# PPR_1_MP.net
KiCad netlist of a schematic drawn in EAGLE
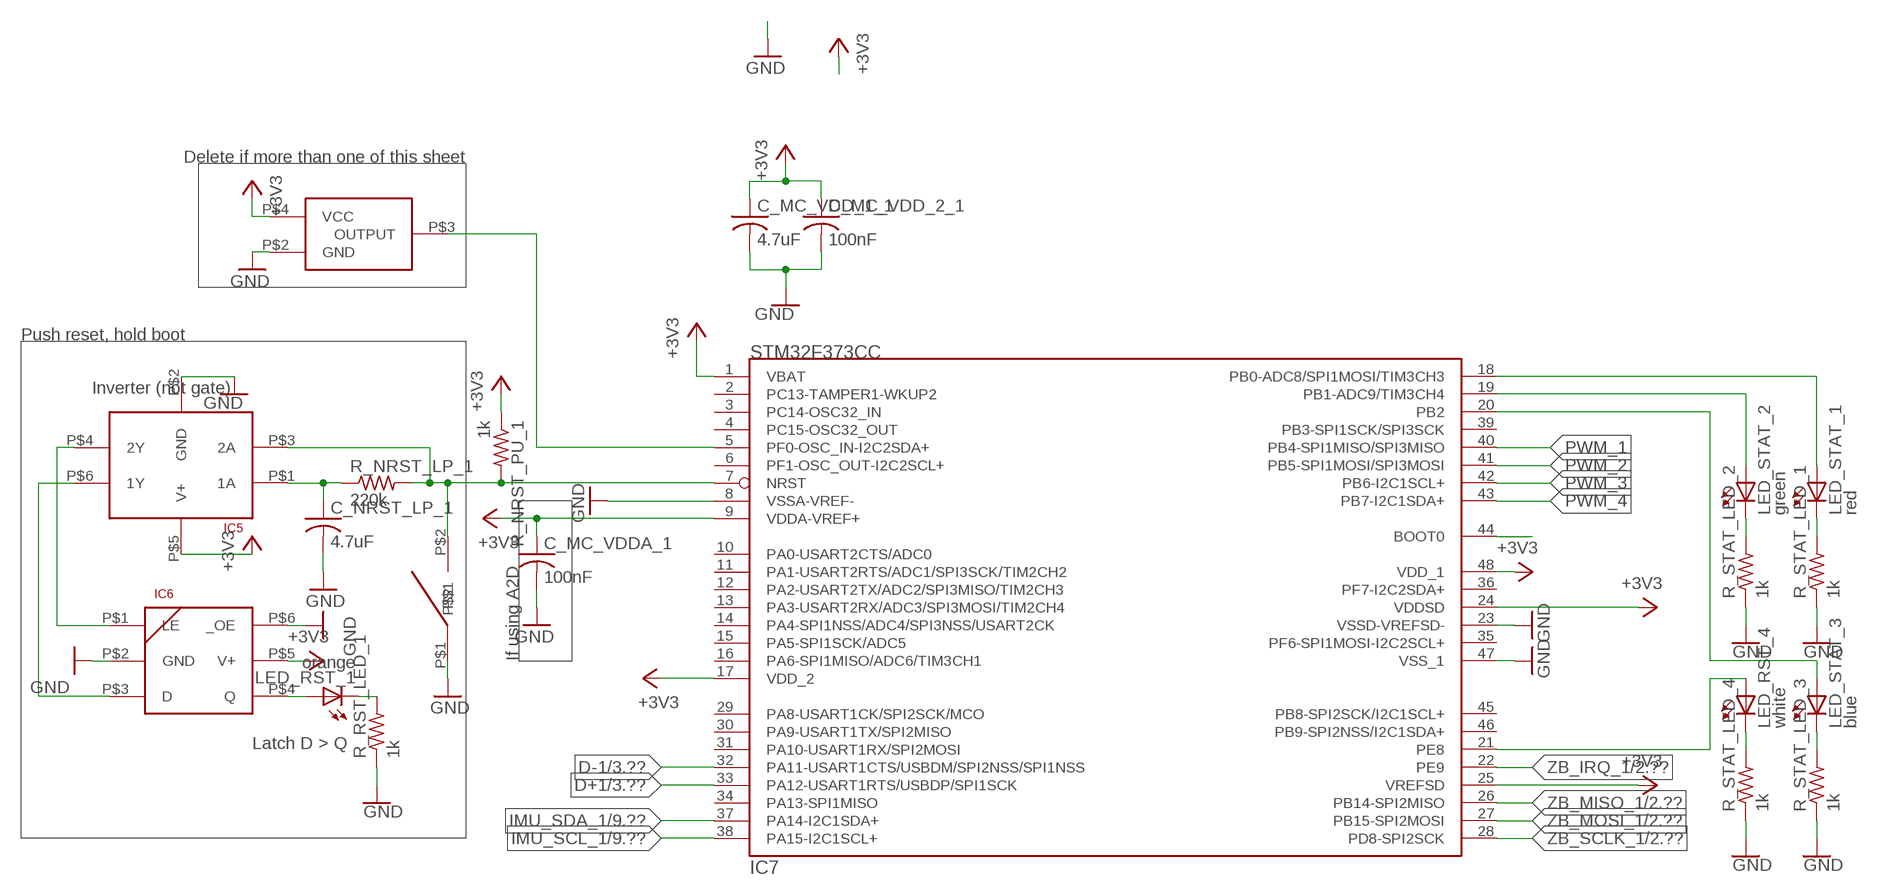
[diagram p0: schematic, sheet 1]
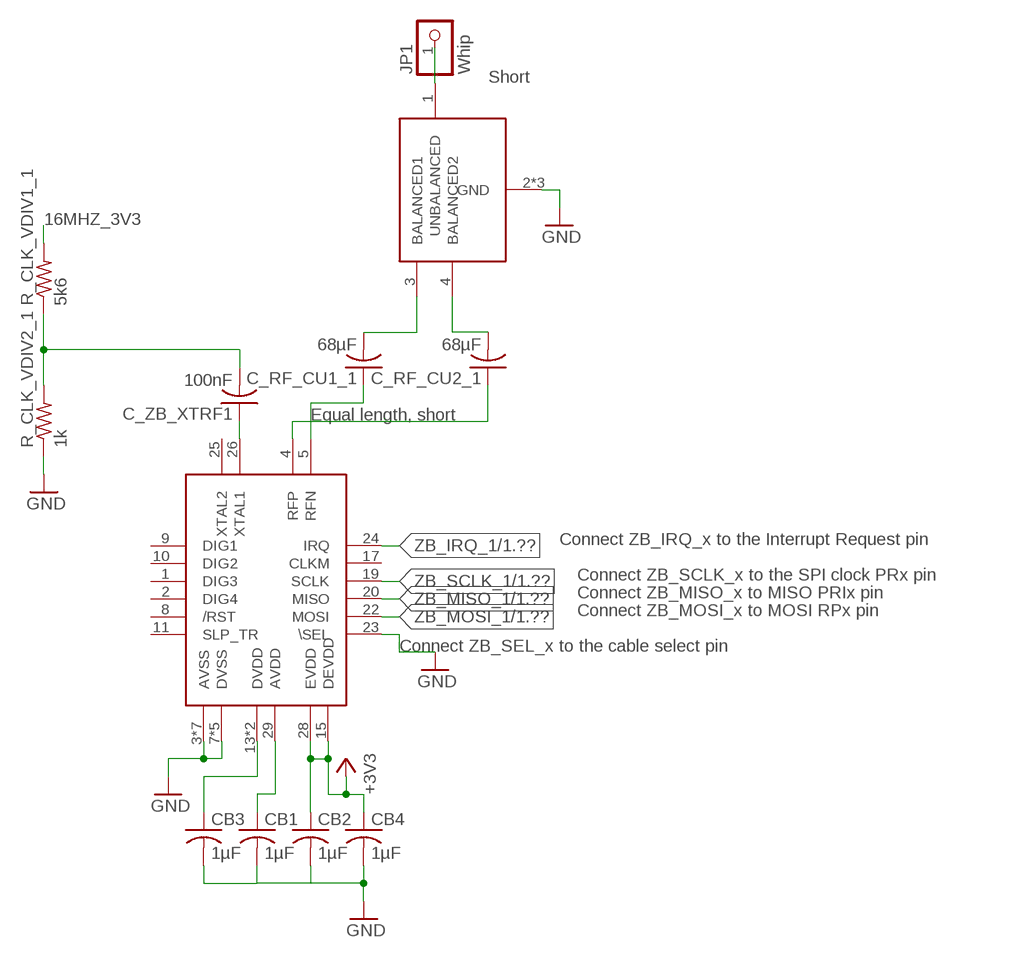
[diagram p1: schematic, sheet 2]
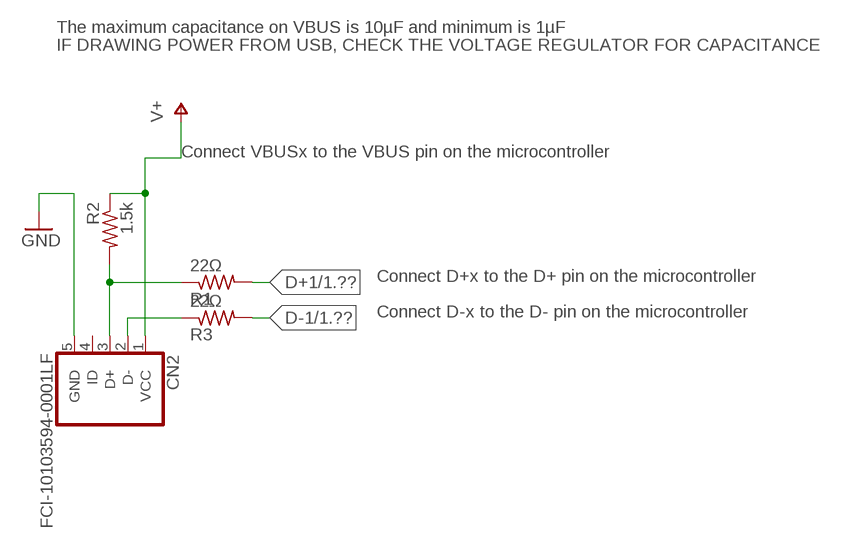
[diagram p2: schematic, sheet 3]
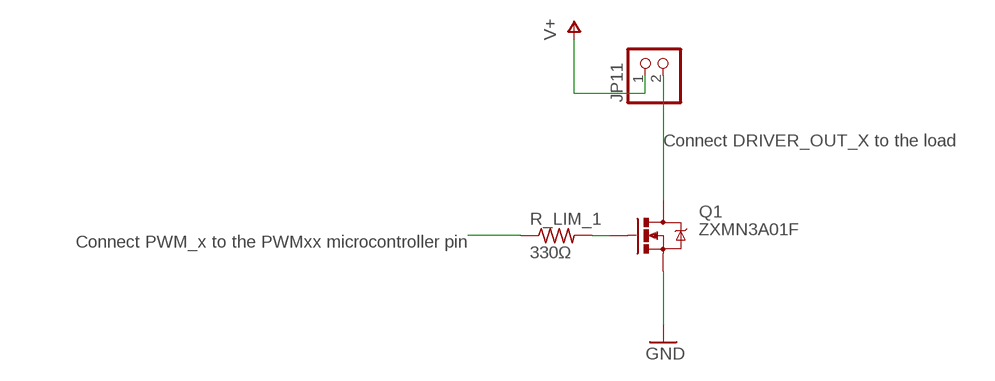
[diagram p3: schematic, sheet 4]
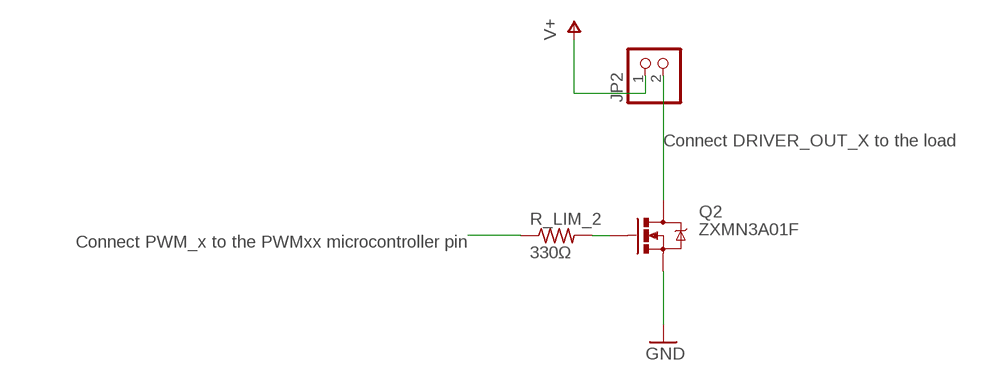
[diagram p4: schematic, sheet 5]
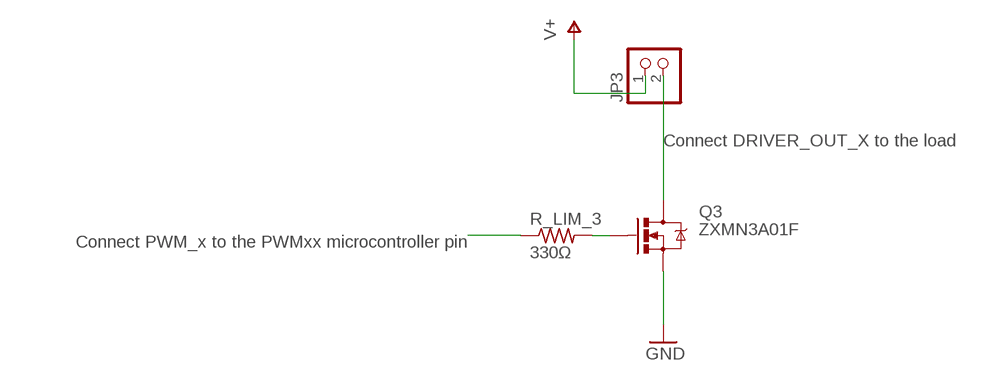
[diagram p5: schematic, sheet 6]
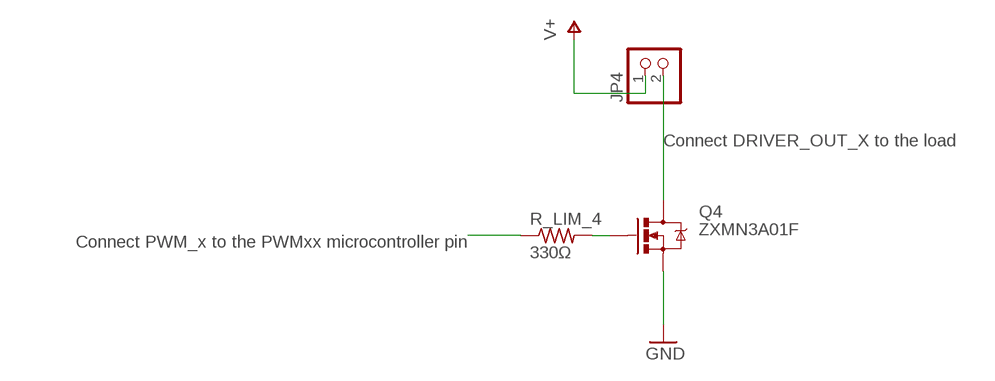
[diagram p6: schematic, sheet 7]
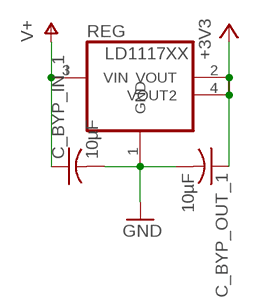
[diagram p7: schematic, sheet 8]
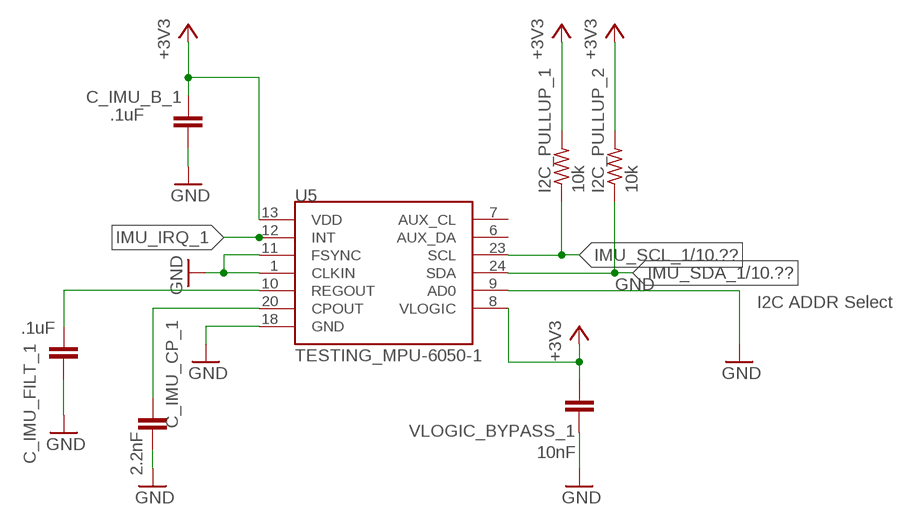
[diagram p8: schematic, sheet 9]
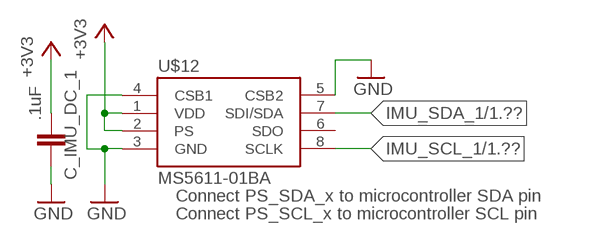
[diagram p9: schematic, sheet 10]
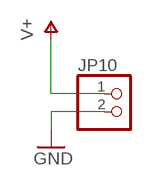
[diagram p10: schematic, sheet 11]

(export (version "E")
  (design (tool "Eeschema 10.0.6"))
  (components
    (comp (ref "JP4")
      (value "PINHD-1X2")
      (footprint "eagle-import:1X02")
      (libsource (lib "eagle-import") (part "PINHD-1X2"))
    )
    (comp (ref "Q4")
      (value "ZXMN3A01F")
      (footprint "eagle-import:SOT23-3")
      (libsource (lib "eagle-import") (part "MOSFET-NCHANNELSMD"))
    )
    (comp (ref "R_LIM_4")
      (value "330Ω")
      (footprint "eagle-import:R0805")
      (libsource (lib "eagle-import") (part "R-US_R0805"))
    )
    (comp (ref "C_IMU_B_1")
      (value ".1uF")
      (footprint "eagle-import:0402-CAP")
      (libsource (lib "eagle-import") (part "CAP0402-CAP"))
    )
    (comp (ref "C_IMU_CP_1")
      (value "2.2nF")
      (footprint "eagle-import:0402-CAP")
      (libsource (lib "eagle-import") (part "CAP0402-CAP"))
    )
    (comp (ref "C_IMU_FILT_1")
      (value ".1uF")
      (footprint "eagle-import:0402-CAP")
      (libsource (lib "eagle-import") (part "CAP0402-CAP"))
    )
    (comp (ref "I2C_PULLUP_1")
      (value "10k")
      (footprint "eagle-import:R0402")
      (libsource (lib "eagle-import") (part "R-US_R0402"))
    )
    (comp (ref "I2C_PULLUP_2")
      (value "10k")
      (footprint "eagle-import:R0402")
      (libsource (lib "eagle-import") (part "R-US_R0402"))
    )
    (comp (ref "U5")
      (value "TESTING_MPU-6050-1")
      (footprint "eagle-import:TESTING_QFN-24-4MM2")
      (libsource (lib "eagle-import") (part "TESTING_MPU-6050-1"))
    )
    (comp (ref "VLOGIC_BYPASS_1")
      (value "10nF")
      (footprint "eagle-import:0402-CAP")
      (libsource (lib "eagle-import") (part "CAP0402-CAP"))
    )
    (comp (ref "JP10")
      (value "PINHD-1X2")
      (footprint "eagle-import:1X02")
      (libsource (lib "eagle-import") (part "PINHD-1X2"))
    )
    (comp (ref "JP3")
      (value "PINHD-1X2")
      (footprint "eagle-import:1X02")
      (libsource (lib "eagle-import") (part "PINHD-1X2"))
    )
    (comp (ref "Q3")
      (value "ZXMN3A01F")
      (footprint "eagle-import:SOT23-3")
      (libsource (lib "eagle-import") (part "MOSFET-NCHANNELSMD"))
    )
    (comp (ref "R_LIM_3")
      (value "330Ω")
      (footprint "eagle-import:R0805")
      (libsource (lib "eagle-import") (part "R-US_R0805"))
    )
    (comp (ref "C_MC_VDDA_1")
      (value "100nF")
      (footprint "eagle-import:C0402")
      (libsource (lib "eagle-import") (part "C-USC0402"))
    )
    (comp (ref "C_MC_VDD_1_1")
      (value "4.7uF")
      (footprint "eagle-import:C0402")
      (libsource (lib "eagle-import") (part "C-USC0402"))
    )
    (comp (ref "C_MC_VDD_2_1")
      (value "100nF")
      (footprint "eagle-import:C0402")
      (libsource (lib "eagle-import") (part "C-USC0402"))
    )
    (comp (ref "C_NRST_LP_1")
      (value "4.7uF")
      (footprint "eagle-import:C0603K")
      (libsource (lib "eagle-import") (part "C-USC0603K"))
    )
    (comp (ref "IC5")
      (value "SN74LVC2G14DCKR")
      (footprint "eagle-import:DCK")
      (libsource (lib "eagle-import") (part "SN74LVC2G14DCKR"))
    )
    (comp (ref "IC6")
      (value "SN74LVC1G373DCKR")
      (footprint "eagle-import:DCK")
      (libsource (lib "eagle-import") (part "SN74LVC1G373DCKR"))
    )
    (comp (ref "IC7")
      (value "STM32F373CC")
      (footprint "eagle-import:LQFP48")
      (libsource (lib "eagle-import") (part "STM32F373CC"))
    )
    (comp (ref "LED_RST_1")
      (value "orange")
      (footprint "eagle-import:CHIPLED_0603")
      (libsource (lib "eagle-import") (part "LEDCHIPLED_0603"))
    )
    (comp (ref "LED_RST_4")
      (value "white")
      (footprint "eagle-import:CHIPLED_0603")
      (libsource (lib "eagle-import") (part "LEDCHIPLED_0603"))
    )
    (comp (ref "LED_STAT_1")
      (value "red")
      (footprint "eagle-import:CHIPLED_0603")
      (libsource (lib "eagle-import") (part "LEDCHIPLED_0603"))
    )
    (comp (ref "LED_STAT_2")
      (value "green")
      (footprint "eagle-import:CHIPLED_0603")
      (libsource (lib "eagle-import") (part "LEDCHIPLED_0603"))
    )
    (comp (ref "LED_STAT_3")
      (value "blue")
      (footprint "eagle-import:CHIPLED_0603")
      (libsource (lib "eagle-import") (part "LEDCHIPLED_0603"))
    )
    (comp (ref "OSC1")
      (value "FOX924B")
      (footprint "eagle-import:4-SMD_5X3.2")
      (libsource (lib "eagle-import") (part "FOX924B"))
    )
    (comp (ref "R_NRST_LP_1")
      (value "220k")
      (footprint "eagle-import:R0402")
      (libsource (lib "eagle-import") (part "resistor_R-US_R0402"))
    )
    (comp (ref "R_NRST_PU_1")
      (value "1k")
      (footprint "eagle-import:R0402")
      (libsource (lib "eagle-import") (part "resistor_R-US_R0402"))
    )
    (comp (ref "R_RST_LED_1")
      (value "1k")
      (footprint "eagle-import:R0402")
      (libsource (lib "eagle-import") (part "resistor_R-US_R0402"))
    )
    (comp (ref "R_STAT_LED_1")
      (value "1k")
      (footprint "eagle-import:R0402")
      (libsource (lib "eagle-import") (part "resistor_R-US_R0402"))
    )
    (comp (ref "R_STAT_LED_2")
      (value "1k")
      (footprint "eagle-import:R0402")
      (libsource (lib "eagle-import") (part "resistor_R-US_R0402"))
    )
    (comp (ref "R_STAT_LED_3")
      (value "1k")
      (footprint "eagle-import:R0402")
      (libsource (lib "eagle-import") (part "resistor_R-US_R0402"))
    )
    (comp (ref "R_STAT_LED_4")
      (value "1k")
      (footprint "eagle-import:R0402")
      (libsource (lib "eagle-import") (part "resistor_R-US_R0402"))
    )
    (comp (ref "SW1")
      (value "B3U")
      (footprint "eagle-import:B3U")
      (libsource (lib "eagle-import") (part "B3U"))
    )
    (comp (ref "BALUN1")
      (value "0896FB15A0100")
      (footprint "eagle-import:0896FB15A0100")
      (libsource (lib "eagle-import") (part "0896FB15A0100"))
    )
    (comp (ref "CB1")
      (value "1µF")
      (footprint "eagle-import:C0603")
      (libsource (lib "eagle-import") (part "C-USC0603"))
    )
    (comp (ref "CB2")
      (value "1µF")
      (footprint "eagle-import:C0603")
      (libsource (lib "eagle-import") (part "C-USC0603"))
    )
    (comp (ref "CB3")
      (value "1µF")
      (footprint "eagle-import:C0603")
      (libsource (lib "eagle-import") (part "C-USC0603"))
    )
    (comp (ref "CB4")
      (value "1µF")
      (footprint "eagle-import:C0603")
      (libsource (lib "eagle-import") (part "C-USC0603"))
    )
    (comp (ref "C_RF_CU1_1")
      (value "68µF")
      (footprint "eagle-import:C0603")
      (libsource (lib "eagle-import") (part "C-USC0603"))
    )
    (comp (ref "C_RF_CU2_1")
      (value "68µF")
      (footprint "eagle-import:C0603")
      (libsource (lib "eagle-import") (part "C-USC0603"))
    )
    (comp (ref "C_ZB_XTRF1")
      (value "100nF")
      (footprint "eagle-import:C0603")
      (libsource (lib "eagle-import") (part "C-USC0603"))
    )
    (comp (ref "JP1")
      (value "Whip")
      (footprint "eagle-import:1X01M")
      (libsource (lib "eagle-import") (part "PINHD-1X01_2.00"))
    )
    (comp (ref "RADIO1")
      (value "AT86RF")
      (footprint "eagle-import:QFNN32")
      (libsource (lib "eagle-import") (part "AT86RF"))
    )
    (comp (ref "R_CLK_VDIV1_1")
      (value "5k6")
      (footprint "eagle-import:R0603")
      (libsource (lib "eagle-import") (part "resistor_R-US_R0603"))
    )
    (comp (ref "R_CLK_VDIV2_1")
      (value "1k")
      (footprint "eagle-import:R0603")
      (libsource (lib "eagle-import") (part "resistor_R-US_R0603"))
    )
    (comp (ref "JP11")
      (value "PINHD-1X2")
      (footprint "eagle-import:1X02")
      (libsource (lib "eagle-import") (part "PINHD-1X2"))
    )
    (comp (ref "Q1")
      (value "ZXMN3A01F")
      (footprint "eagle-import:SOT23-3")
      (libsource (lib "eagle-import") (part "MOSFET-NCHANNELSMD"))
    )
    (comp (ref "R_LIM_1")
      (value "330Ω")
      (footprint "eagle-import:R0805")
      (libsource (lib "eagle-import") (part "R-US_R0805"))
    )
    (comp (ref "C_IMU_DC_1")
      (value ".1uF")
      (footprint "eagle-import:0402-CAP")
      (libsource (lib "eagle-import") (part "CAP0402-CAP"))
    )
    (comp (ref "U$12")
      (value "MS5611-01BA")
      (footprint "eagle-import:MS5611-01BA")
      (libsource (lib "eagle-import") (part "MS5611-01BA"))
    )
    (comp (ref "C_BYP_IN_1")
      (value "10µF")
      (footprint "eagle-import:C1206")
      (libsource (lib "eagle-import") (part "C-USC1206"))
    )
    (comp (ref "C_BYP_OUT_1")
      (value "10µF")
      (footprint "eagle-import:C0603")
      (libsource (lib "eagle-import") (part "C-USC0603"))
    )
    (comp (ref "REG")
      (value "LD1117XX")
      (footprint "eagle-import:SOT-223")
      (libsource (lib "eagle-import") (part "LD1117XX"))
    )
    (comp (ref "JP2")
      (value "PINHD-1X2")
      (footprint "eagle-import:1X02")
      (libsource (lib "eagle-import") (part "PINHD-1X2"))
    )
    (comp (ref "Q2")
      (value "ZXMN3A01F")
      (footprint "eagle-import:SOT23-3")
      (libsource (lib "eagle-import") (part "MOSFET-NCHANNELSMD"))
    )
    (comp (ref "R_LIM_2")
      (value "330Ω")
      (footprint "eagle-import:R0805")
      (libsource (lib "eagle-import") (part "R-US_R0805"))
    )
    (comp (ref "CN2")
      (value "FCI-10103594-0001LF")
      (footprint "eagle-import:FCI-10103594-0001LF")
      (libsource (lib "eagle-import") (part "USB-RECEPTABLE"))
    )
    (comp (ref "R1")
      (value "22Ω")
      (footprint "eagle-import:R0402")
      (libsource (lib "eagle-import") (part "resistor_R-US_R0402"))
    )
    (comp (ref "R2")
      (value "1.5k")
      (footprint "eagle-import:R0402")
      (libsource (lib "eagle-import") (part "resistor_R-US_R0402"))
    )
    (comp (ref "R3")
      (value "22Ω")
      (footprint "eagle-import:R0402")
      (libsource (lib "eagle-import") (part "resistor_R-US_R0402"))
    )
  )
  (nets
    (net (code "1") (name "+3V3") (class "Default")
      (node (ref "CB2") (pin "1") (pinfunction "1_1") (pintype "passive"))
      (node (ref "CB4") (pin "1") (pinfunction "1_1") (pintype "passive"))
      (node (ref "C_BYP_OUT_1") (pin "1") (pinfunction "1_1") (pintype "passive"))
      (node (ref "C_IMU_B_1") (pin "2") (pinfunction "2_2") (pintype "passive"))
      (node (ref "C_IMU_DC_1") (pin "2") (pinfunction "2_2") (pintype "passive"))
      (node (ref "C_MC_VDDA_1") (pin "1") (pinfunction "1_1") (pintype "passive"))
      (node (ref "C_MC_VDD_1_1") (pin "1") (pinfunction "1_1") (pintype "passive"))
      (node (ref "C_MC_VDD_2_1") (pin "1") (pinfunction "1_1") (pintype "passive"))
      (node (ref "I2C_PULLUP_1") (pin "2") (pinfunction "2_2") (pintype "passive"))
      (node (ref "I2C_PULLUP_2") (pin "2") (pinfunction "2_2") (pintype "passive"))
      (node (ref "IC5") (pin "P$5") (pinfunction "V+_P$5") (pintype "bidirectional"))
      (node (ref "IC6") (pin "P$5") (pinfunction "V+_P$5") (pintype "bidirectional"))
      (node (ref "IC7") (pin "1") (pinfunction "VBAT_1") (pintype "power_in"))
      (node (ref "IC7") (pin "17") (pinfunction "VDD_2_17") (pintype "bidirectional"))
      (node (ref "IC7") (pin "24") (pinfunction "VDDSD_24") (pintype "power_in"))
      (node (ref "IC7") (pin "25") (pinfunction "VREFSD_25") (pintype "bidirectional"))
      (node (ref "IC7") (pin "48") (pinfunction "VDD_1_48") (pintype "power_in"))
      (node (ref "IC7") (pin "9") (pinfunction "VDDA-VREF+_9") (pintype "power_in"))
      (node (ref "OSC1") (pin "P$4") (pinfunction "VCC_P$4") (pintype "bidirectional"))
      (node (ref "RADIO1") (pin "15") (pinfunction "DEVDD_15") (pintype "power_in"))
      (node (ref "RADIO1") (pin "28") (pinfunction "EVDD_28") (pintype "power_in"))
      (node (ref "REG") (pin "2") (pinfunction "VOUT_2") (pintype "output"))
      (node (ref "REG") (pin "4") (pinfunction "VOUT2_4") (pintype "output"))
      (node (ref "R_NRST_PU_1") (pin "1") (pinfunction "1_1") (pintype "passive"))
      (node (ref "U$12") (pin "1") (pinfunction "VDD_1") (pintype "bidirectional"))
      (node (ref "U$12") (pin "2") (pinfunction "PS_2") (pintype "bidirectional"))
      (node (ref "U5") (pin "13") (pinfunction "VDD_13") (pintype "bidirectional"))
      (node (ref "U5") (pin "8") (pinfunction "VLOGIC_8") (pintype "bidirectional"))
      (node (ref "VLOGIC_BYPASS_1") (pin "2") (pinfunction "2_2") (pintype "passive"))
    )
    (net (code "2") (name "16MHZ_3V3") (class "Default")
      (node (ref "IC7") (pin "5") (pinfunction "PF0-OSC_IN-I2C2SDA+_5") (pintype "bidirectional"))
      (node (ref "OSC1") (pin "P$3") (pinfunction "OUTPUT_P$3") (pintype "bidirectional"))
      (node (ref "R_CLK_VDIV1_1") (pin "2") (pinfunction "2_2") (pintype "passive"))
    )
    (net (code "3") (name "BOOT0_1") (class "Default")
      (node (ref "IC5") (pin "P$6") (pinfunction "1Y_P$6") (pintype "bidirectional"))
      (node (ref "IC6") (pin "P$3") (pinfunction "D_P$3") (pintype "bidirectional"))
      (node (ref "IC7") (pin "44") (pinfunction "BOOT0_44") (pintype "input"))
    )
    (net (code "4") (name "D+1") (class "Default")
      (node (ref "IC7") (pin "33") (pinfunction "PA12-USART1RTS/USBDP/SPI1SCK_33") (pintype "bidirectional"))
      (node (ref "R1") (pin "2") (pinfunction "2_2") (pintype "passive"))
    )
    (net (code "5") (name "D-1") (class "Default")
      (node (ref "IC7") (pin "32") (pinfunction "PA11-USART1CTS/USBDM/SPI2NSS/SPI1NSS_32") (pintype "bidirectional"))
      (node (ref "R3") (pin "2") (pinfunction "2_2") (pintype "passive"))
    )
    (net (code "6") (name "GND") (class "Default")
      (node (ref "BALUN1") (pin "2") (pinfunction "GND_2") (pintype "power_in"))
      (node (ref "BALUN1") (pin "5") (pinfunction "GND_5") (pintype "power_in"))
      (node (ref "BALUN1") (pin "6") (pinfunction "GND_6") (pintype "power_in"))
      (node (ref "CB1") (pin "2") (pinfunction "2_2") (pintype "passive"))
      (node (ref "CB2") (pin "2") (pinfunction "2_2") (pintype "passive"))
      (node (ref "CB3") (pin "2") (pinfunction "2_2") (pintype "passive"))
      (node (ref "CB4") (pin "2") (pinfunction "2_2") (pintype "passive"))
      (node (ref "CN2") (pin "5") (pinfunction "GND_5") (pintype "bidirectional"))
      (node (ref "C_BYP_IN_1") (pin "2") (pinfunction "2_2") (pintype "passive"))
      (node (ref "C_BYP_OUT_1") (pin "2") (pinfunction "2_2") (pintype "passive"))
      (node (ref "C_IMU_B_1") (pin "1") (pinfunction "1_1") (pintype "passive"))
      (node (ref "C_IMU_CP_1") (pin "1") (pinfunction "1_1") (pintype "passive"))
      (node (ref "C_IMU_DC_1") (pin "1") (pinfunction "1_1") (pintype "passive"))
      (node (ref "C_IMU_FILT_1") (pin "1") (pinfunction "1_1") (pintype "passive"))
      (node (ref "C_MC_VDDA_1") (pin "2") (pinfunction "2_2") (pintype "passive"))
      (node (ref "C_MC_VDD_1_1") (pin "2") (pinfunction "2_2") (pintype "passive"))
      (node (ref "C_MC_VDD_2_1") (pin "2") (pinfunction "2_2") (pintype "passive"))
      (node (ref "C_NRST_LP_1") (pin "2") (pinfunction "2_2") (pintype "passive"))
      (node (ref "IC5") (pin "P$2") (pinfunction "GND_P$2") (pintype "bidirectional"))
      (node (ref "IC6") (pin "P$2") (pinfunction "GND_P$2") (pintype "bidirectional"))
      (node (ref "IC6") (pin "P$6") (pinfunction "_OE_P$6") (pintype "bidirectional"))
      (node (ref "IC7") (pin "23") (pinfunction "VSSD-VREFSD-_23") (pintype "power_in"))
      (node (ref "IC7") (pin "47") (pinfunction "VSS_1_47") (pintype "power_in"))
      (node (ref "IC7") (pin "8") (pinfunction "VSSA-VREF-_8") (pintype "power_in"))
      (node (ref "JP10") (pin "2") (pinfunction "2_2") (pintype "passive"))
      (node (ref "OSC1") (pin "P$2") (pinfunction "GND_P$2") (pintype "bidirectional"))
      (node (ref "Q1") (pin "2") (pinfunction "S_2") (pintype "passive"))
      (node (ref "Q2") (pin "2") (pinfunction "S_2") (pintype "passive"))
      (node (ref "Q3") (pin "2") (pinfunction "S_2") (pintype "passive"))
      (node (ref "Q4") (pin "2") (pinfunction "S_2") (pintype "passive"))
      (node (ref "RADIO1") (pin "12") (pinfunction "DVSS_12") (pintype "power_in"))
      (node (ref "RADIO1") (pin "16") (pinfunction "DVSS_16") (pintype "power_in"))
      (node (ref "RADIO1") (pin "18") (pinfunction "DVSS_18") (pintype "power_in"))
      (node (ref "RADIO1") (pin "21") (pinfunction "DVSS_21") (pintype "power_in"))
      (node (ref "RADIO1") (pin "23") (pinfunction "\\SEL_23") (pintype "input"))
      (node (ref "RADIO1") (pin "27") (pinfunction "AVSS_27") (pintype "power_in"))
      (node (ref "RADIO1") (pin "3") (pinfunction "AVSS_3") (pintype "power_in"))
      (node (ref "RADIO1") (pin "30") (pinfunction "AVSS_30") (pintype "power_in"))
      (node (ref "RADIO1") (pin "31") (pinfunction "AVSS_31") (pintype "power_in"))
      (node (ref "RADIO1") (pin "32") (pinfunction "AVSS_32") (pintype "power_in"))
      (node (ref "RADIO1") (pin "6") (pinfunction "AVSS_6") (pintype "power_in"))
      (node (ref "RADIO1") (pin "7") (pinfunction "DVSS_7") (pintype "power_in"))
      (node (ref "RADIO1") (pin "EXP") (pinfunction "AVSS_EXP") (pintype "power_in"))
      (node (ref "REG") (pin "1") (pinfunction "GND_1") (pintype "power_in"))
      (node (ref "R_CLK_VDIV2_1") (pin "1") (pinfunction "1_1") (pintype "passive"))
      (node (ref "R_RST_LED_1") (pin "1") (pinfunction "1_1") (pintype "passive"))
      (node (ref "R_STAT_LED_1") (pin "1") (pinfunction "1_1") (pintype "passive"))
      (node (ref "R_STAT_LED_2") (pin "1") (pinfunction "1_1") (pintype "passive"))
      (node (ref "R_STAT_LED_3") (pin "1") (pinfunction "1_1") (pintype "passive"))
      (node (ref "R_STAT_LED_4") (pin "1") (pinfunction "1_1") (pintype "passive"))
      (node (ref "SW1") (pin "P$1") (pinfunction "P$1_P$1") (pintype "bidirectional"))
      (node (ref "U$12") (pin "3") (pinfunction "GND_3") (pintype "bidirectional"))
      (node (ref "U$12") (pin "4") (pinfunction "CSB1_4") (pintype "bidirectional"))
      (node (ref "U$12") (pin "5") (pinfunction "CSB2_5") (pintype "bidirectional"))
      (node (ref "U5") (pin "1") (pinfunction "CLKIN_1") (pintype "bidirectional"))
      (node (ref "U5") (pin "11") (pinfunction "FSYNC_11") (pintype "bidirectional"))
      (node (ref "U5") (pin "18") (pinfunction "GND_18") (pintype "bidirectional"))
      (node (ref "U5") (pin "9") (pinfunction "AD0_9") (pintype "bidirectional"))
      (node (ref "VLOGIC_BYPASS_1") (pin "1") (pinfunction "1_1") (pintype "passive"))
    )
    (net (code "7") (name "IMU_IRQ_1") (class "Default")
      (node (ref "U5") (pin "12") (pinfunction "INT_12") (pintype "bidirectional"))
    )
    (net (code "8") (name "IMU_SCL_1") (class "Default")
      (node (ref "I2C_PULLUP_1") (pin "1") (pinfunction "1_1") (pintype "passive"))
      (node (ref "IC7") (pin "38") (pinfunction "PA15-I2C1SCL+_38") (pintype "bidirectional"))
      (node (ref "U$12") (pin "8") (pinfunction "SCLK_8") (pintype "bidirectional"))
      (node (ref "U5") (pin "23") (pinfunction "SCL_23") (pintype "bidirectional"))
    )
    (net (code "9") (name "IMU_SDA_1") (class "Default")
      (node (ref "I2C_PULLUP_2") (pin "1") (pinfunction "1_1") (pintype "passive"))
      (node (ref "IC7") (pin "37") (pinfunction "PA14-I2C1SDA+_37") (pintype "bidirectional"))
      (node (ref "U$12") (pin "7") (pinfunction "SDI/SDA_7") (pintype "bidirectional"))
      (node (ref "U5") (pin "24") (pinfunction "SDA_24") (pintype "bidirectional"))
    )
    (net (code "10") (name "Net-(BALUN1-BALANCED1)") (class "Default")
      (node (ref "BALUN1") (pin "3") (pinfunction "BALANCED1_3") (pintype "bidirectional"))
      (node (ref "C_RF_CU1_1") (pin "2") (pinfunction "2_2") (pintype "passive"))
    )
    (net (code "11") (name "Net-(BALUN1-BALANCED2)") (class "Default")
      (node (ref "BALUN1") (pin "4") (pinfunction "BALANCED2_4") (pintype "bidirectional"))
      (node (ref "C_RF_CU2_1") (pin "2") (pinfunction "2_2") (pintype "passive"))
    )
    (net (code "12") (name "Net-(BALUN1-UNBALANCED)") (class "Default")
      (node (ref "BALUN1") (pin "1") (pinfunction "UNBALANCED_1") (pintype "bidirectional"))
      (node (ref "JP1") (pin "1") (pinfunction "1_1") (pintype "passive"))
    )
    (net (code "13") (name "Net-(CB3-Pad1)") (class "Default")
      (node (ref "CB3") (pin "1") (pinfunction "1_1") (pintype "passive"))
      (node (ref "RADIO1") (pin "13") (pinfunction "DVDD_13") (pintype "power_in"))
      (node (ref "RADIO1") (pin "14") (pinfunction "DVDD_14") (pintype "power_in"))
    )
    (net (code "14") (name "Net-(CN2-D+)") (class "Default")
      (node (ref "CN2") (pin "3") (pinfunction "D+_3") (pintype "bidirectional"))
      (node (ref "R1") (pin "1") (pinfunction "1_1") (pintype "passive"))
      (node (ref "R2") (pin "2") (pinfunction "2_2") (pintype "passive"))
    )
    (net (code "15") (name "Net-(CN2-D-)") (class "Default")
      (node (ref "CN2") (pin "2") (pinfunction "D-_2") (pintype "bidirectional"))
      (node (ref "R3") (pin "1") (pinfunction "1_1") (pintype "passive"))
    )
    (net (code "16") (name "Net-(C_ZB_XTRF1-Pad2)") (class "Default")
      (node (ref "C_ZB_XTRF1") (pin "2") (pinfunction "2_2") (pintype "passive"))
      (node (ref "R_CLK_VDIV1_1") (pin "1") (pinfunction "1_1") (pintype "passive"))
      (node (ref "R_CLK_VDIV2_1") (pin "2") (pinfunction "2_2") (pintype "passive"))
    )
    (net (code "17") (name "Net-(IC5-1A)") (class "Default")
      (node (ref "C_NRST_LP_1") (pin "1") (pinfunction "1_1") (pintype "passive"))
      (node (ref "IC5") (pin "P$1") (pinfunction "1A_P$1") (pintype "bidirectional"))
      (node (ref "R_NRST_LP_1") (pin "1") (pinfunction "1_1") (pintype "passive"))
    )
    (net (code "18") (name "Net-(IC5-2A)") (class "Default")
      (node (ref "IC5") (pin "P$3") (pinfunction "2A_P$3") (pintype "bidirectional"))
      (node (ref "IC7") (pin "7") (pinfunction "NRST_7") (pintype "bidirectional"))
      (node (ref "R_NRST_LP_1") (pin "2") (pinfunction "2_2") (pintype "passive"))
      (node (ref "R_NRST_PU_1") (pin "2") (pinfunction "2_2") (pintype "passive"))
      (node (ref "SW1") (pin "P$2") (pinfunction "P$2_P$2") (pintype "bidirectional"))
    )
    (net (code "19") (name "Net-(IC5-2Y)") (class "Default")
      (node (ref "IC5") (pin "P$4") (pinfunction "2Y_P$4") (pintype "bidirectional"))
      (node (ref "IC6") (pin "P$1") (pinfunction "LE_P$1") (pintype "bidirectional"))
    )
    (net (code "20") (name "Net-(IC6-Q)") (class "Default")
      (node (ref "IC6") (pin "P$4") (pinfunction "Q_P$4") (pintype "bidirectional"))
      (node (ref "LED_RST_1") (pin "A") (pinfunction "A_A") (pintype "passive"))
    )
    (net (code "21") (name "Net-(IC7-PB0-ADC8{slash}SPI1MOSI{slash}TIM3CH3)") (class "Default")
      (node (ref "IC7") (pin "18") (pinfunction "PB0-ADC8/SPI1MOSI/TIM3CH3_18") (pintype "bidirectional"))
      (node (ref "LED_STAT_1") (pin "A") (pinfunction "A_A") (pintype "passive"))
    )
    (net (code "22") (name "Net-(IC7-PB1-ADC9{slash}TIM3CH4)") (class "Default")
      (node (ref "IC7") (pin "19") (pinfunction "PB1-ADC9/TIM3CH4_19") (pintype "bidirectional"))
      (node (ref "LED_STAT_2") (pin "A") (pinfunction "A_A") (pintype "passive"))
    )
    (net (code "23") (name "Net-(IC7-PB2)") (class "Default")
      (node (ref "IC7") (pin "20") (pinfunction "PB2_20") (pintype "bidirectional"))
      (node (ref "LED_STAT_3") (pin "A") (pinfunction "A_A") (pintype "passive"))
    )
    (net (code "24") (name "Net-(IC7-PE8)") (class "Default")
      (node (ref "IC7") (pin "21") (pinfunction "PE8_21") (pintype "bidirectional"))
      (node (ref "LED_RST_4") (pin "A") (pinfunction "A_A") (pintype "passive"))
    )
    (net (code "25") (name "Net-(LED_RST_1-PadC)") (class "Default")
      (node (ref "LED_RST_1") (pin "C") (pinfunction "C_C") (pintype "passive"))
      (node (ref "R_RST_LED_1") (pin "2") (pinfunction "2_2") (pintype "passive"))
    )
    (net (code "26") (name "Net-(LED_RST_4-PadC)") (class "Default")
      (node (ref "LED_RST_4") (pin "C") (pinfunction "C_C") (pintype "passive"))
      (node (ref "R_STAT_LED_4") (pin "2") (pinfunction "2_2") (pintype "passive"))
    )
    (net (code "27") (name "Net-(LED_STAT_1-PadC)") (class "Default")
      (node (ref "LED_STAT_1") (pin "C") (pinfunction "C_C") (pintype "passive"))
      (node (ref "R_STAT_LED_1") (pin "2") (pinfunction "2_2") (pintype "passive"))
    )
    (net (code "28") (name "Net-(LED_STAT_2-PadC)") (class "Default")
      (node (ref "LED_STAT_2") (pin "C") (pinfunction "C_C") (pintype "passive"))
      (node (ref "R_STAT_LED_2") (pin "2") (pinfunction "2_2") (pintype "passive"))
    )
    (net (code "29") (name "Net-(LED_STAT_3-PadC)") (class "Default")
      (node (ref "LED_STAT_3") (pin "C") (pinfunction "C_C") (pintype "passive"))
      (node (ref "R_STAT_LED_3") (pin "2") (pinfunction "2_2") (pintype "passive"))
    )
    (net (code "30") (name "Net-(Q1-D)") (class "Default")
      (node (ref "JP11") (pin "2") (pinfunction "2_2") (pintype "passive"))
      (node (ref "Q1") (pin "3") (pinfunction "D_3") (pintype "passive"))
    )
    (net (code "31") (name "Net-(Q1-G)") (class "Default")
      (node (ref "Q1") (pin "1") (pinfunction "G_1") (pintype "passive"))
      (node (ref "R_LIM_1") (pin "2") (pinfunction "2_2") (pintype "passive"))
    )
    (net (code "32") (name "Net-(Q2-D)") (class "Default")
      (node (ref "JP2") (pin "2") (pinfunction "2_2") (pintype "passive"))
      (node (ref "Q2") (pin "3") (pinfunction "D_3") (pintype "passive"))
    )
    (net (code "33") (name "Net-(Q2-G)") (class "Default")
      (node (ref "Q2") (pin "1") (pinfunction "G_1") (pintype "passive"))
      (node (ref "R_LIM_2") (pin "2") (pinfunction "2_2") (pintype "passive"))
    )
    (net (code "34") (name "Net-(Q3-D)") (class "Default")
      (node (ref "JP3") (pin "2") (pinfunction "2_2") (pintype "passive"))
      (node (ref "Q3") (pin "3") (pinfunction "D_3") (pintype "passive"))
    )
    (net (code "35") (name "Net-(Q3-G)") (class "Default")
      (node (ref "Q3") (pin "1") (pinfunction "G_1") (pintype "passive"))
      (node (ref "R_LIM_3") (pin "2") (pinfunction "2_2") (pintype "passive"))
    )
    (net (code "36") (name "Net-(Q4-D)") (class "Default")
      (node (ref "JP4") (pin "2") (pinfunction "2_2") (pintype "passive"))
      (node (ref "Q4") (pin "3") (pinfunction "D_3") (pintype "passive"))
    )
    (net (code "37") (name "Net-(Q4-G)") (class "Default")
      (node (ref "Q4") (pin "1") (pinfunction "G_1") (pintype "passive"))
      (node (ref "R_LIM_4") (pin "2") (pinfunction "2_2") (pintype "passive"))
    )
    (net (code "38") (name "Net-(RADIO1-AVDD)") (class "Default")
      (node (ref "CB1") (pin "1") (pinfunction "1_1") (pintype "passive"))
      (node (ref "RADIO1") (pin "29") (pinfunction "AVDD_29") (pintype "power_in"))
    )
    (net (code "39") (name "Net-(RADIO1-RFN)") (class "Default")
      (node (ref "C_RF_CU1_1") (pin "1") (pinfunction "1_1") (pintype "passive"))
      (node (ref "RADIO1") (pin "5") (pinfunction "RFN_5") (pintype "bidirectional"))
    )
    (net (code "40") (name "Net-(RADIO1-RFP)") (class "Default")
      (node (ref "C_RF_CU2_1") (pin "1") (pinfunction "1_1") (pintype "passive"))
      (node (ref "RADIO1") (pin "4") (pinfunction "RFP_4") (pintype "bidirectional"))
    )
    (net (code "41") (name "Net-(RADIO1-XTAL1)") (class "Default")
      (node (ref "C_ZB_XTRF1") (pin "1") (pinfunction "1_1") (pintype "passive"))
      (node (ref "RADIO1") (pin "26") (pinfunction "XTAL1_26") (pintype "bidirectional"))
    )
    (net (code "42") (name "Net-(U5-CPOUT)") (class "Default")
      (node (ref "C_IMU_CP_1") (pin "2") (pinfunction "2_2") (pintype "passive"))
      (node (ref "U5") (pin "20") (pinfunction "CPOUT_20") (pintype "bidirectional"))
    )
    (net (code "43") (name "Net-(U5-REGOUT)") (class "Default")
      (node (ref "C_IMU_FILT_1") (pin "2") (pinfunction "2_2") (pintype "passive"))
      (node (ref "U5") (pin "10") (pinfunction "REGOUT_10") (pintype "bidirectional"))
    )
    (net (code "44") (name "PWM_1") (class "Default")
      (node (ref "IC7") (pin "40") (pinfunction "PB4-SPI1MISO/SPI3MISO_40") (pintype "bidirectional"))
      (node (ref "R_LIM_1") (pin "1") (pinfunction "1_1") (pintype "passive"))
    )
    (net (code "45") (name "PWM_2") (class "Default")
      (node (ref "IC7") (pin "41") (pinfunction "PB5-SPI1MOSI/SPI3MOSI_41") (pintype "bidirectional"))
      (node (ref "R_LIM_2") (pin "1") (pinfunction "1_1") (pintype "passive"))
    )
    (net (code "46") (name "PWM_3") (class "Default")
      (node (ref "IC7") (pin "42") (pinfunction "PB6-I2C1SCL+_42") (pintype "bidirectional"))
      (node (ref "R_LIM_3") (pin "1") (pinfunction "1_1") (pintype "passive"))
    )
    (net (code "47") (name "PWM_4") (class "Default")
      (node (ref "IC7") (pin "43") (pinfunction "PB7-I2C1SDA+_43") (pintype "bidirectional"))
      (node (ref "R_LIM_4") (pin "1") (pinfunction "1_1") (pintype "passive"))
    )
    (net (code "48") (name "V+") (class "Default")
      (node (ref "CN2") (pin "1") (pinfunction "VCC_1") (pintype "bidirectional"))
      (node (ref "C_BYP_IN_1") (pin "1") (pinfunction "1_1") (pintype "passive"))
      (node (ref "JP10") (pin "1") (pinfunction "1_1") (pintype "passive"))
      (node (ref "JP11") (pin "1") (pinfunction "1_1") (pintype "passive"))
      (node (ref "JP2") (pin "1") (pinfunction "1_1") (pintype "passive"))
      (node (ref "JP3") (pin "1") (pinfunction "1_1") (pintype "passive"))
      (node (ref "JP4") (pin "1") (pinfunction "1_1") (pintype "passive"))
      (node (ref "R2") (pin "1") (pinfunction "1_1") (pintype "passive"))
      (node (ref "REG") (pin "3") (pinfunction "VIN_3") (pintype "input"))
    )
    (net (code "49") (name "ZB_IRQ_1") (class "Default")
      (node (ref "IC7") (pin "22") (pinfunction "PE9_22") (pintype "bidirectional"))
      (node (ref "RADIO1") (pin "24") (pinfunction "IRQ_24") (pintype "output"))
    )
    (net (code "50") (name "ZB_MISO_1") (class "Default")
      (node (ref "IC7") (pin "26") (pinfunction "PB14-SPI2MISO_26") (pintype "bidirectional"))
      (node (ref "RADIO1") (pin "20") (pinfunction "MISO_20") (pintype "output"))
    )
    (net (code "51") (name "ZB_MOSI_1") (class "Default")
      (node (ref "IC7") (pin "27") (pinfunction "PB15-SPI2MOSI_27") (pintype "bidirectional"))
      (node (ref "RADIO1") (pin "22") (pinfunction "MOSI_22") (pintype "input"))
    )
    (net (code "52") (name "ZB_SCLK_1") (class "Default")
      (node (ref "IC7") (pin "28") (pinfunction "PD8-SPI2SCK_28") (pintype "bidirectional"))
      (node (ref "RADIO1") (pin "19") (pinfunction "SCLK_19") (pintype "input"))
    )
    (net (code "53") (name "unconnected-(CN2-ID-Pad4)") (class "Default")
      (node (ref "CN2") (pin "4") (pinfunction "ID_4") (pintype "bidirectional"))
    )
    (net (code "54") (name "unconnected-(IC7-PA0-USART2CTS{slash}ADC0-Pad10)") (class "Default")
      (node (ref "IC7") (pin "10") (pinfunction "PA0-USART2CTS/ADC0_10") (pintype "bidirectional"))
    )
    (net (code "55") (name "unconnected-(IC7-PA1-USART2RTS{slash}ADC1{slash}SPI3SCK{slash}TIM2CH2-Pad11)") (class "Default")
      (node (ref "IC7") (pin "11") (pinfunction "PA1-USART2RTS/ADC1/SPI3SCK/TIM2CH2_11") (pintype "bidirectional"))
    )
    (net (code "56") (name "unconnected-(IC7-PA2-USART2TX{slash}ADC2{slash}SPI3MISO{slash}TIM2CH3-Pad12)") (class "Default")
      (node (ref "IC7") (pin "12") (pinfunction "PA2-USART2TX/ADC2/SPI3MISO/TIM2CH3_12") (pintype "bidirectional"))
    )
    (net (code "57") (name "unconnected-(IC7-PA3-USART2RX{slash}ADC3{slash}SPI3MOSI{slash}TIM2CH4-Pad13)") (class "Default")
      (node (ref "IC7") (pin "13") (pinfunction "PA3-USART2RX/ADC3/SPI3MOSI/TIM2CH4_13") (pintype "bidirectional"))
    )
    (net (code "58") (name "unconnected-(IC7-PA4-SPI1NSS{slash}ADC4{slash}SPI3NSS{slash}USART2CK-Pad14)") (class "Default")
      (node (ref "IC7") (pin "14") (pinfunction "PA4-SPI1NSS/ADC4/SPI3NSS/USART2CK_14") (pintype "bidirectional"))
    )
    (net (code "59") (name "unconnected-(IC7-PA5-SPI1SCK{slash}ADC5-Pad15)") (class "Default")
      (node (ref "IC7") (pin "15") (pinfunction "PA5-SPI1SCK/ADC5_15") (pintype "bidirectional"))
    )
    (net (code "60") (name "unconnected-(IC7-PA6-SPI1MISO{slash}ADC6{slash}TIM3CH1-Pad16)") (class "Default")
      (node (ref "IC7") (pin "16") (pinfunction "PA6-SPI1MISO/ADC6/TIM3CH1_16") (pintype "bidirectional"))
    )
    (net (code "61") (name "unconnected-(IC7-PA8-USART1CK{slash}SPI2SCK{slash}MCO-Pad29)") (class "Default")
      (node (ref "IC7") (pin "29") (pinfunction "PA8-USART1CK/SPI2SCK/MCO_29") (pintype "bidirectional"))
    )
    (net (code "62") (name "unconnected-(IC7-PA9-USART1TX{slash}SPI2MISO-Pad30)") (class "Default")
      (node (ref "IC7") (pin "30") (pinfunction "PA9-USART1TX/SPI2MISO_30") (pintype "bidirectional"))
    )
    (net (code "63") (name "unconnected-(IC7-PA10-USART1RX{slash}SPI2MOSI-Pad31)") (class "Default")
      (node (ref "IC7") (pin "31") (pinfunction "PA10-USART1RX/SPI2MOSI_31") (pintype "bidirectional"))
    )
    (net (code "64") (name "unconnected-(IC7-PA13-SPI1MISO-Pad34)") (class "Default")
      (node (ref "IC7") (pin "34") (pinfunction "PA13-SPI1MISO_34") (pintype "bidirectional"))
    )
    (net (code "65") (name "unconnected-(IC7-PB3-SPI1SCK{slash}SPI3SCK-Pad39)") (class "Default")
      (node (ref "IC7") (pin "39") (pinfunction "PB3-SPI1SCK/SPI3SCK_39") (pintype "bidirectional"))
    )
    (net (code "66") (name "unconnected-(IC7-PB8-SPI2SCK{slash}I2C1SCL+-Pad45)") (class "Default")
      (node (ref "IC7") (pin "45") (pinfunction "PB8-SPI2SCK/I2C1SCL+_45") (pintype "bidirectional"))
    )
    (net (code "67") (name "unconnected-(IC7-PB9-SPI2NSS{slash}I2C1SDA+-Pad46)") (class "Default")
      (node (ref "IC7") (pin "46") (pinfunction "PB9-SPI2NSS/I2C1SDA+_46") (pintype "bidirectional"))
    )
    (net (code "68") (name "unconnected-(IC7-PC13-TAMPER1-WKUP2-Pad2)") (class "Default")
      (node (ref "IC7") (pin "2") (pinfunction "PC13-TAMPER1-WKUP2_2") (pintype "bidirectional"))
    )
    (net (code "69") (name "unconnected-(IC7-PC14-OSC32_IN-Pad3)") (class "Default")
      (node (ref "IC7") (pin "3") (pinfunction "PC14-OSC32_IN_3") (pintype "bidirectional"))
    )
    (net (code "70") (name "unconnected-(IC7-PC15-OSC32_OUT-Pad4)") (class "Default")
      (node (ref "IC7") (pin "4") (pinfunction "PC15-OSC32_OUT_4") (pintype "bidirectional"))
    )
    (net (code "71") (name "unconnected-(IC7-PF1-OSC_OUT-I2C2SCL+-Pad6)") (class "Default")
      (node (ref "IC7") (pin "6") (pinfunction "PF1-OSC_OUT-I2C2SCL+_6") (pintype "bidirectional"))
    )
    (net (code "72") (name "unconnected-(IC7-PF6-SPI1MOSI-I2C2SCL+-Pad35)") (class "Default")
      (node (ref "IC7") (pin "35") (pinfunction "PF6-SPI1MOSI-I2C2SCL+_35") (pintype "bidirectional"))
    )
    (net (code "73") (name "unconnected-(IC7-PF7-I2C2SDA+-Pad36)") (class "Default")
      (node (ref "IC7") (pin "36") (pinfunction "PF7-I2C2SDA+_36") (pintype "bidirectional"))
    )
    (net (code "74") (name "unconnected-(RADIO1-CLKM-Pad17)") (class "Default")
      (node (ref "RADIO1") (pin "17") (pinfunction "CLKM_17") (pintype "output"))
    )
    (net (code "75") (name "unconnected-(RADIO1-DIG1-Pad9)") (class "Default")
      (node (ref "RADIO1") (pin "9") (pinfunction "DIG1_9") (pintype "output"))
    )
    (net (code "76") (name "unconnected-(RADIO1-DIG2-Pad10)") (class "Default")
      (node (ref "RADIO1") (pin "10") (pinfunction "DIG2_10") (pintype "output"))
    )
    (net (code "77") (name "unconnected-(RADIO1-DIG3-Pad1)") (class "Default")
      (node (ref "RADIO1") (pin "1") (pinfunction "DIG3_1") (pintype "output"))
    )
    (net (code "78") (name "unconnected-(RADIO1-DIG4-Pad2)") (class "Default")
      (node (ref "RADIO1") (pin "2") (pinfunction "DIG4_2") (pintype "output"))
    )
    (net (code "79") (name "unconnected-(RADIO1-SLP_TR-Pad11)") (class "Default")
      (node (ref "RADIO1") (pin "11") (pinfunction "SLP_TR_11") (pintype "bidirectional"))
    )
    (net (code "80") (name "unconnected-(RADIO1-XTAL2-Pad25)") (class "Default")
      (node (ref "RADIO1") (pin "25") (pinfunction "XTAL2_25") (pintype "bidirectional"))
    )
    (net (code "81") (name "unconnected-(RADIO1-{slash}RST-Pad8)") (class "Default")
      (node (ref "RADIO1") (pin "8") (pinfunction "/RST_8") (pintype "input"))
    )
    (net (code "82") (name "unconnected-(U$12-SDO-Pad6)") (class "Default")
      (node (ref "U$12") (pin "6") (pinfunction "SDO_6") (pintype "bidirectional"))
    )
    (net (code "83") (name "unconnected-(U5-AUX_CL-Pad7)") (class "Default")
      (node (ref "U5") (pin "7") (pinfunction "AUX_CL_7") (pintype "bidirectional"))
    )
    (net (code "84") (name "unconnected-(U5-AUX_DA-Pad6)") (class "Default")
      (node (ref "U5") (pin "6") (pinfunction "AUX_DA_6") (pintype "bidirectional"))
    )
  )
)
